# Alim_Schematic.net
KiCad netlist of a schematic drawn in Altium Designer
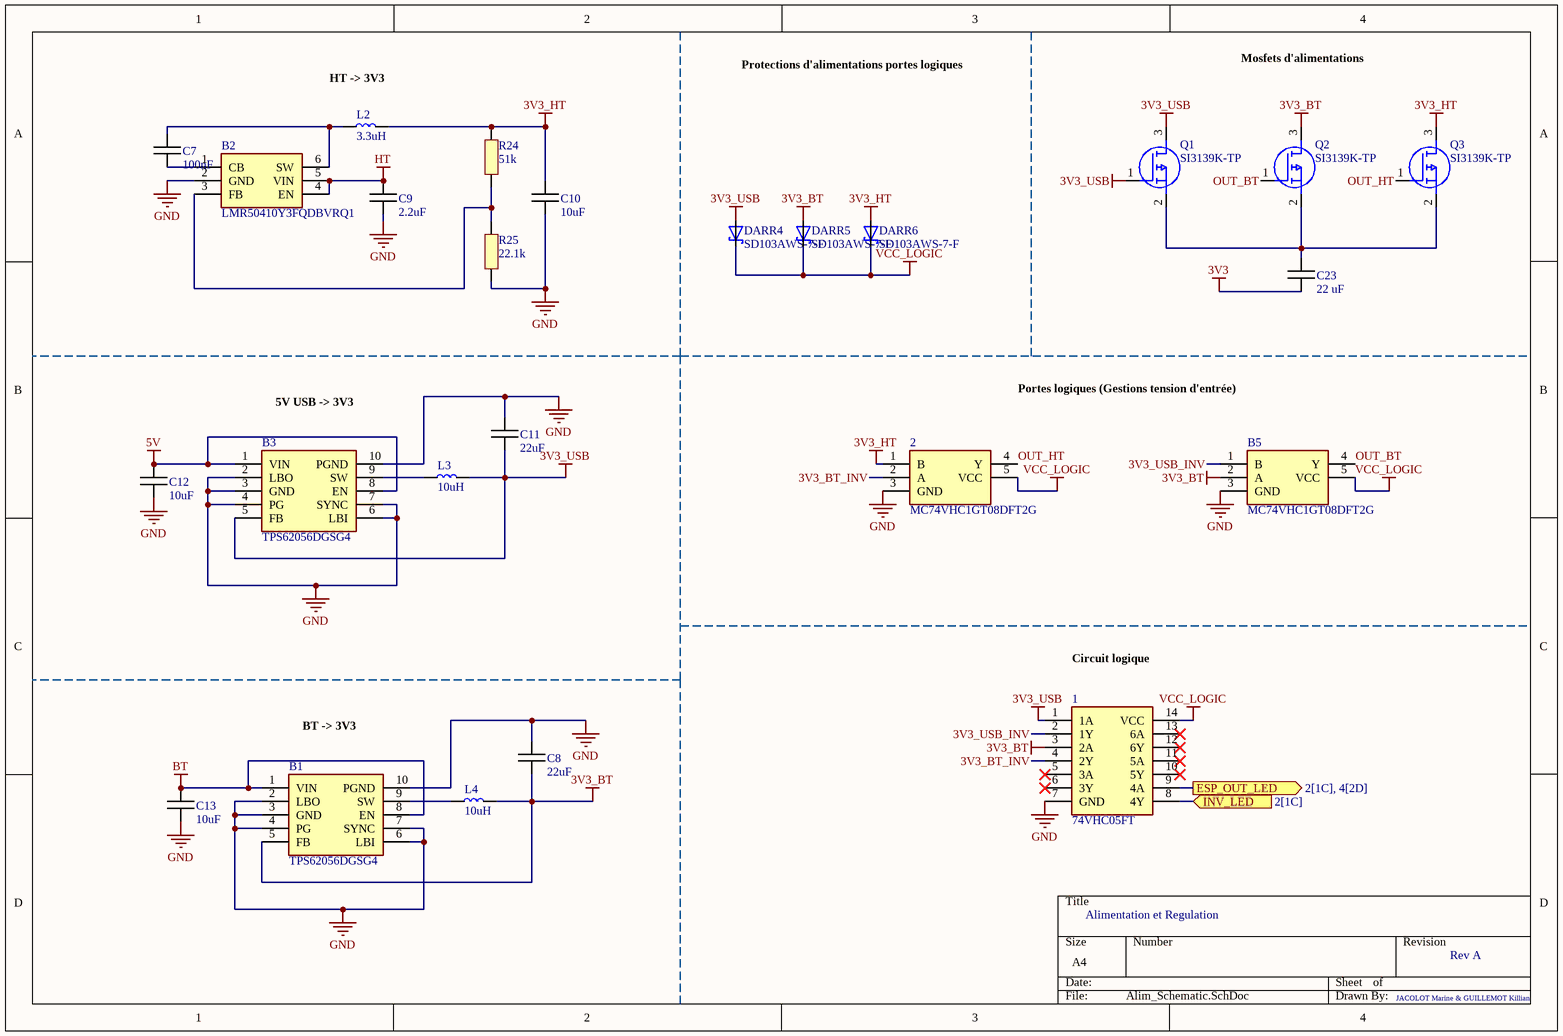
[diagram p0: Alim_Schematic.SchDoc]

(export (version "E")
  (design (tool "Eeschema 10.0.6"))
  (components
    (comp (ref "1")
      (value "74VHC05FT")
      (footprint "SOP65P640X120-14N")
      (description "Logic Gates CMOS LOGIC IC INVERTER")
      (fields (field (name "MOUSER PART NUMBER") "757-74VHC05FT"))
      (libsource (lib "SCHLibrary") (part "74VHC05FT"))
    )
    (comp (ref "2")
      (value "MC74VHC1GT08DFT2G")
      (footprint "SOT65P210X110-5N")
      (description "Single 2-Input AND Gate, TTL Level")
      (libsource (lib "SCHLibrary") (part "MC74VHC1GT08DFT2G"))
    )
    (comp (ref "B1")
      (value "TPS62056DGSG4")
      (footprint "SOP50P490X110-10N")
      (fields (field (name "MOUSER PART NUMBER") "595-TPS62056DGSG4"))
      (libsource (lib "SCHLibrary") (part "TPS62056DGSG4"))
    )
    (comp (ref "B2")
      (value "LMR50410Y3FQDBVRQ1")
      (footprint "SOT95P280X145-6N")
      (fields (field (name "MOUSER PART NUMBER") "595-R50410Y3FQDBVRQ1"))
      (libsource (lib "SCHLibrary") (part "LMR50410Y3FQDBVRQ1"))
    )
    (comp (ref "B3")
      (value "TPS62056DGSG4")
      (footprint "SOP50P490X110-10N")
      (fields (field (name "MOUSER PART NUMBER") "595-TPS62056DGSG4"))
      (libsource (lib "SCHLibrary") (part "TPS62056DGSG4"))
    )
    (comp (ref "B5")
      (value "MC74VHC1GT08DFT2G")
      (footprint "SOT65P210X110-5N")
      (description "Single 2-Input AND Gate, TTL Level")
      (libsource (lib "SCHLibrary") (part "MC74VHC1GT08DFT2G"))
    )
    (comp (ref "C7")
      (value "100nF")
      (footprint "CAPC1005X06N")
      (libsource (lib "SCHLibrary") (part "Capacitor"))
    )
    (comp (ref "C8")
      (value "22uF")
      (footprint "CAPC1005X06N")
      (libsource (lib "SCHLibrary") (part "Capacitor"))
    )
    (comp (ref "C9")
      (value "2.2uF")
      (footprint "CAPC1005X06N")
      (libsource (lib "SCHLibrary") (part "Capacitor"))
    )
    (comp (ref "C10")
      (value "10uF")
      (footprint "CAPC1005X06N")
      (libsource (lib "SCHLibrary") (part "Capacitor"))
    )
    (comp (ref "C11")
      (value "22uF")
      (footprint "CAPC1005X06N")
      (libsource (lib "SCHLibrary") (part "Capacitor"))
    )
    (comp (ref "C12")
      (value "10uF")
      (footprint "CAPC1005X06N")
      (libsource (lib "SCHLibrary") (part "Capacitor"))
    )
    (comp (ref "C13")
      (value "10uF")
      (footprint "CAPC1005X06N")
      (libsource (lib "SCHLibrary") (part "Capacitor"))
    )
    (comp (ref "C23")
      (value "22 uF")
      (footprint "CAPC1005X06N")
      (libsource (lib "SCHLibrary") (part "Capacitor"))
    )
    (comp (ref "DARR4")
      (value "SD103AWS-7-F")
      (footprint "SD103AWS-7-F")
      (description "Diode Array 3 Independent Schottky 40V 175mA Surface Mount 6-TSSOP, SC-88, SOT-363")
      (libsource (lib "SCHLibrary") (part "SD103AWS-7-F"))
    )
    (comp (ref "DARR5")
      (value "SD103AWS-7-F")
      (footprint "SD103AWS-7-F")
      (description "Diode Array 3 Independent Schottky 40V 175mA Surface Mount 6-TSSOP, SC-88, SOT-363")
      (libsource (lib "SCHLibrary") (part "SD103AWS-7-F"))
    )
    (comp (ref "DARR6")
      (value "SD103AWS-7-F")
      (footprint "SD103AWS-7-F")
      (description "Diode Array 3 Independent Schottky 40V 175mA Surface Mount 6-TSSOP, SC-88, SOT-363")
      (libsource (lib "SCHLibrary") (part "SD103AWS-7-F"))
    )
    (comp (ref "L2")
      (value "3.3uH")
      (footprint "LQPC1005X06N")
      (libsource (lib "SCHLibrary") (part "Bobine"))
    )
    (comp (ref "L3") (value "10uH") (footprint "LQPC1005X06N") (libsource (lib "SCHLibrary") (part "Bobine")))
    (comp (ref "L4") (value "10uH") (footprint "LQPC1005X06N") (libsource (lib "SCHLibrary") (part "Bobine")))
    (comp (ref "Q1")
      (value "SI3139K-TP")
      (footprint "SI3139K-TP")
      (description "MOSFET P-Channel MOSFET")
      (libsource (lib "SCHLibrary") (part "SI3139K-TP"))
    )
    (comp (ref "Q2")
      (value "SI3139K-TP")
      (footprint "SI3139K-TP")
      (description "MOSFET P-Channel MOSFET")
      (libsource (lib "SCHLibrary") (part "SI3139K-TP"))
    )
    (comp (ref "Q3")
      (value "SI3139K-TP")
      (footprint "SI3139K-TP")
      (description "MOSFET P-Channel MOSFET")
      (libsource (lib "SCHLibrary") (part "SI3139K-TP"))
    )
    (comp (ref "R24")
      (value "51k")
      (footprint "RESC1005X06N")
      (libsource (lib "SCHLibrary") (part "Resistor"))
    )
    (comp (ref "R25") (value "22.1k") (footprint "RESC1005X06N") (libsource (lib "") (part "Resistor_1")))
  )
  (nets
    (net (code "1") (name "/3V3_BT_INV") (class "Default")
      (node (ref "1") (pin "4") (pinfunction "2Y_4") (pintype "passive"))
      (node (ref "2") (pin "2") (pinfunction "A_2") (pintype "passive"))
    )
    (net (code "2") (name "/3V3_USB_INV") (class "Default")
      (node (ref "1") (pin "2") (pinfunction "1Y_2") (pintype "passive"))
      (node (ref "B5") (pin "1") (pinfunction "B_1") (pintype "passive"))
    )
    (net (code "3") (name "/ESP_OUT_LED") (class "Default")
      (node (ref "1") (pin "9") (pinfunction "4A_9") (pintype "passive"))
    )
    (net (code "4") (name "/INV_LED") (class "Default")
      (node (ref "1") (pin "8") (pinfunction "4Y_8") (pintype "passive"))
    )
    (net (code "5") (name "/OUT_BT") (class "Default")
      (node (ref "B5") (pin "4") (pinfunction "Y_4") (pintype "passive"))
      (node (ref "Q2") (pin "1") (pinfunction "G_1") (pintype "passive"))
    )
    (net (code "6") (name "/OUT_HT") (class "Default")
      (node (ref "2") (pin "4") (pinfunction "Y_4") (pintype "passive"))
      (node (ref "Q3") (pin "1") (pinfunction "G_1") (pintype "passive"))
    )
    (net (code "7") (name "3V3") (class "Default")
      (node (ref "C23") (pin "1") (pinfunction "1_1") (pintype "passive"))
    )
    (net (code "8") (name "3V3_BT") (class "Default")
      (node (ref "1") (pin "3") (pinfunction "2A_3") (pintype "passive"))
      (node (ref "B1") (pin "5") (pinfunction "FB_5") (pintype "passive"))
      (node (ref "B5") (pin "2") (pinfunction "A_2") (pintype "passive"))
      (node (ref "C8") (pin "1") (pinfunction "1_1") (pintype "passive"))
      (node (ref "DARR5") (pin "2") (pinfunction "A_2") (pintype "passive"))
      (node (ref "L4") (pin "2") (pinfunction "2_2") (pintype "passive"))
      (node (ref "Q2") (pin "3") (pinfunction "D_3") (pintype "passive"))
    )
    (net (code "9") (name "3V3_HT") (class "Default")
      (node (ref "2") (pin "1") (pinfunction "B_1") (pintype "passive"))
      (node (ref "C10") (pin "1") (pinfunction "1_1") (pintype "passive"))
      (node (ref "DARR6") (pin "2") (pinfunction "A_2") (pintype "passive"))
      (node (ref "L2") (pin "2") (pinfunction "2_2") (pintype "passive"))
      (node (ref "Q3") (pin "3") (pinfunction "D_3") (pintype "passive"))
      (node (ref "R24") (pin "1") (pinfunction "1_1") (pintype "passive"))
    )
    (net (code "10") (name "3V3_USB") (class "Default")
      (node (ref "1") (pin "1") (pinfunction "1A_1") (pintype "passive"))
      (node (ref "B3") (pin "5") (pinfunction "FB_5") (pintype "passive"))
      (node (ref "C11") (pin "1") (pinfunction "1_1") (pintype "passive"))
      (node (ref "DARR4") (pin "2") (pinfunction "A_2") (pintype "passive"))
      (node (ref "L3") (pin "2") (pinfunction "2_2") (pintype "passive"))
      (node (ref "Q1") (pin "1") (pinfunction "G_1") (pintype "passive"))
      (node (ref "Q1") (pin "3") (pinfunction "D_3") (pintype "passive"))
    )
    (net (code "11") (name "5V") (class "Default")
      (node (ref "B3") (pin "1") (pinfunction "VIN_1") (pintype "passive"))
      (node (ref "B3") (pin "8") (pinfunction "EN_8") (pintype "passive"))
      (node (ref "C12") (pin "1") (pinfunction "1_1") (pintype "passive"))
    )
    (net (code "12") (name "BT") (class "Default")
      (node (ref "B1") (pin "1") (pinfunction "VIN_1") (pintype "passive"))
      (node (ref "B1") (pin "8") (pinfunction "EN_8") (pintype "passive"))
      (node (ref "C13") (pin "1") (pinfunction "1_1") (pintype "passive"))
    )
    (net (code "13") (name "GND") (class "Default")
      (node (ref "1") (pin "7") (pinfunction "GND_7") (pintype "passive"))
      (node (ref "2") (pin "3") (pinfunction "GND_3") (pintype "passive"))
      (node (ref "B1") (pin "10") (pinfunction "PGND_10") (pintype "passive"))
      (node (ref "B1") (pin "2") (pinfunction "LBO_2") (pintype "passive"))
      (node (ref "B1") (pin "3") (pinfunction "GND_3") (pintype "passive"))
      (node (ref "B1") (pin "4") (pinfunction "PG_4") (pintype "passive"))
      (node (ref "B1") (pin "6") (pinfunction "LBI_6") (pintype "passive"))
      (node (ref "B1") (pin "7") (pinfunction "SYNC_7") (pintype "passive"))
      (node (ref "B2") (pin "2") (pinfunction "GND_2") (pintype "passive"))
      (node (ref "B3") (pin "10") (pinfunction "PGND_10") (pintype "passive"))
      (node (ref "B3") (pin "2") (pinfunction "LBO_2") (pintype "passive"))
      (node (ref "B3") (pin "3") (pinfunction "GND_3") (pintype "passive"))
      (node (ref "B3") (pin "4") (pinfunction "PG_4") (pintype "passive"))
      (node (ref "B3") (pin "6") (pinfunction "LBI_6") (pintype "passive"))
      (node (ref "B3") (pin "7") (pinfunction "SYNC_7") (pintype "passive"))
      (node (ref "B5") (pin "3") (pinfunction "GND_3") (pintype "passive"))
      (node (ref "C10") (pin "2") (pinfunction "2_2") (pintype "passive"))
      (node (ref "C11") (pin "2") (pinfunction "2_2") (pintype "passive"))
      (node (ref "C12") (pin "2") (pinfunction "2_2") (pintype "passive"))
      (node (ref "C13") (pin "2") (pinfunction "2_2") (pintype "passive"))
      (node (ref "C8") (pin "2") (pinfunction "2_2") (pintype "passive"))
      (node (ref "C9") (pin "2") (pinfunction "2_2") (pintype "passive"))
      (node (ref "R25") (pin "1") (pinfunction "1_1") (pintype "passive"))
    )
    (net (code "14") (name "HT") (class "Default")
      (node (ref "B2") (pin "4") (pinfunction "EN_4") (pintype "passive"))
      (node (ref "B2") (pin "5") (pinfunction "VIN_5") (pintype "passive"))
      (node (ref "C9") (pin "1") (pinfunction "1_1") (pintype "passive"))
    )
    (net (code "15") (name "Net-(B1-SW)") (class "Default")
      (node (ref "B1") (pin "9") (pinfunction "SW_9") (pintype "passive"))
      (node (ref "L4") (pin "1") (pinfunction "1_1") (pintype "passive"))
    )
    (net (code "16") (name "Net-(B2-CB)") (class "Default")
      (node (ref "B2") (pin "1") (pinfunction "CB_1") (pintype "passive"))
      (node (ref "C7") (pin "2") (pinfunction "2_2") (pintype "passive"))
    )
    (net (code "17") (name "Net-(B2-FB)") (class "Default")
      (node (ref "B2") (pin "3") (pinfunction "FB_3") (pintype "passive"))
      (node (ref "R24") (pin "2") (pinfunction "2_2") (pintype "passive"))
      (node (ref "R25") (pin "2") (pinfunction "2_2") (pintype "passive"))
    )
    (net (code "18") (name "Net-(B2-SW)") (class "Default")
      (node (ref "B2") (pin "6") (pinfunction "SW_6") (pintype "passive"))
      (node (ref "C7") (pin "1") (pinfunction "1_1") (pintype "passive"))
      (node (ref "L2") (pin "1") (pinfunction "1_1") (pintype "passive"))
    )
    (net (code "19") (name "Net-(B3-SW)") (class "Default")
      (node (ref "B3") (pin "9") (pinfunction "SW_9") (pintype "passive"))
      (node (ref "L3") (pin "1") (pinfunction "1_1") (pintype "passive"))
    )
    (net (code "20") (name "Net-(Q1-S)") (class "Default")
      (node (ref "C23") (pin "2") (pinfunction "2_2") (pintype "passive"))
      (node (ref "Q1") (pin "2") (pinfunction "S_2") (pintype "passive"))
      (node (ref "Q2") (pin "2") (pinfunction "S_2") (pintype "passive"))
      (node (ref "Q3") (pin "2") (pinfunction "S_2") (pintype "passive"))
    )
    (net (code "21") (name "VCC_LOGIC") (class "Default")
      (node (ref "1") (pin "14") (pinfunction "VCC_14") (pintype "passive"))
      (node (ref "2") (pin "5") (pinfunction "VCC_5") (pintype "passive"))
      (node (ref "B5") (pin "5") (pinfunction "VCC_5") (pintype "passive"))
      (node (ref "DARR4") (pin "1") (pinfunction "C_1") (pintype "passive"))
      (node (ref "DARR5") (pin "1") (pinfunction "C_1") (pintype "passive"))
      (node (ref "DARR6") (pin "1") (pinfunction "C_1") (pintype "passive"))
    )
    (net (code "22") (name "unconnected-(1-3A-Pad5)") (class "Default")
      (node (ref "1") (pin "5") (pinfunction "3A_5") (pintype "passive+no_connect"))
    )
    (net (code "23") (name "unconnected-(1-3Y-Pad6)") (class "Default")
      (node (ref "1") (pin "6") (pinfunction "3Y_6") (pintype "passive+no_connect"))
    )
    (net (code "24") (name "unconnected-(1-5A-Pad11)") (class "Default")
      (node (ref "1") (pin "11") (pinfunction "5A_11") (pintype "passive+no_connect"))
    )
    (net (code "25") (name "unconnected-(1-5Y-Pad10)") (class "Default")
      (node (ref "1") (pin "10") (pinfunction "5Y_10") (pintype "passive+no_connect"))
    )
    (net (code "26") (name "unconnected-(1-6A-Pad13)") (class "Default")
      (node (ref "1") (pin "13") (pinfunction "6A_13") (pintype "passive+no_connect"))
    )
    (net (code "27") (name "unconnected-(1-6Y-Pad12)") (class "Default")
      (node (ref "1") (pin "12") (pinfunction "6Y_12") (pintype "passive+no_connect"))
    )
  )
)
